# HM11.net
KiCad netlist of a schematic drawn in EAGLE
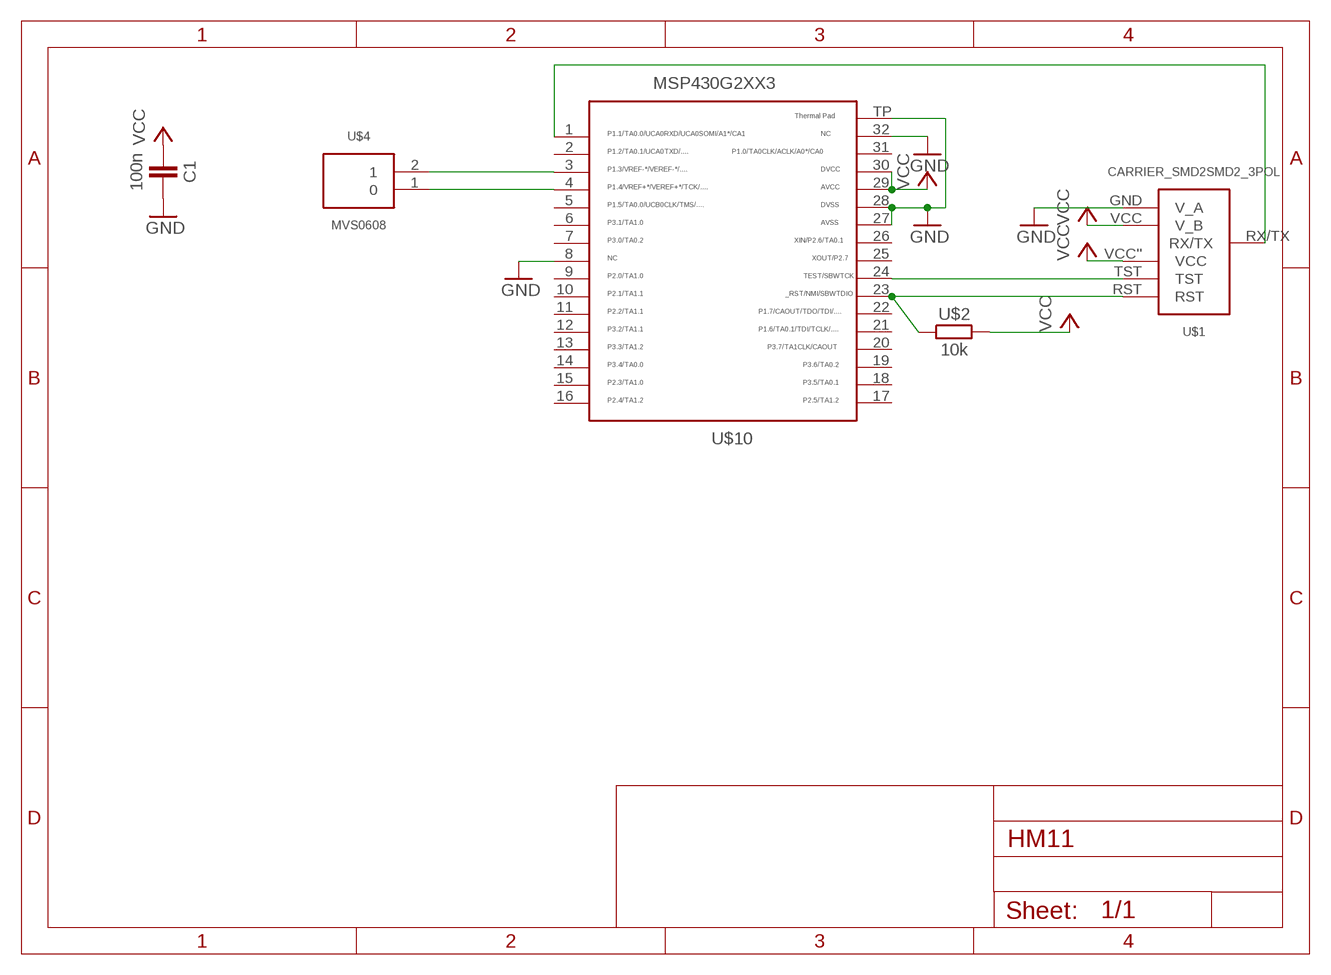
[diagram p0: schematic, sheet 1]

(export (version "E")
  (design (tool "Eeschema 10.0.6"))
  (components
    (comp (ref "C1")
      (value "100n")
      (footprint "eagle-import:603")
      (libsource (lib "eagle-import") (part "CAPACITOR"))
    )
    (comp (ref "U$1")
      (value "CARRIER_SMD2SMD2_3POL")
      (footprint "eagle-import:CARRIER_SMD2_3POL")
      (libsource (lib "eagle-import") (part "CARRIER_SMD2SMD2_3POL"))
    )
    (comp (ref "U$2")
      (value "10k")
      (footprint "eagle-import:603")
      (libsource (lib "eagle-import") (part "RESISTOR0603"))
    )
    (comp (ref "U$4")
      (value "MVS0608")
      (footprint "eagle-import:MVS06O8")
      (libsource (lib "eagle-import") (part "MVS0608"))
    )
    (comp (ref "U$10")
      (value "MSP430G2553")
      (footprint "eagle-import:QFN32")
      (libsource (lib "eagle-import") (part "MSP430G2553"))
    )
  )
  (nets
    (net (code "1") (name "GND") (class "Default")
      (node (ref "C1") (pin "2") (pinfunction "2_2") (pintype "passive"))
      (node (ref "U$1") (pin "GND") (pinfunction "V_A_GND") (pintype "bidirectional"))
      (node (ref "U$10") (pin "27") (pinfunction "27_27") (pintype "bidirectional"))
      (node (ref "U$10") (pin "28") (pinfunction "28_28") (pintype "bidirectional"))
      (node (ref "U$10") (pin "32") (pinfunction "32_32") (pintype "bidirectional"))
      (node (ref "U$10") (pin "8") (pinfunction "8_8") (pintype "bidirectional"))
      (node (ref "U$10") (pin "TP") (pinfunction "TP_TP") (pintype "bidirectional"))
    )
    (net (code "2") (name "Net-(U$1-PadRST)") (class "Default")
      (node (ref "U$1") (pin "RST") (pinfunction "RST_RST") (pintype "bidirectional"))
      (node (ref "U$10") (pin "23") (pinfunction "23_23") (pintype "bidirectional"))
      (node (ref "U$2") (pin "1") (pinfunction "1_1") (pintype "passive"))
    )
    (net (code "3") (name "Net-(U$1-PadRX{slash}TX)") (class "Default")
      (node (ref "U$1") (pin "RX/TX") (pinfunction "RX/TX_RX/TX") (pintype "bidirectional"))
      (node (ref "U$10") (pin "1") (pinfunction "1_1") (pintype "bidirectional"))
    )
    (net (code "4") (name "Net-(U$1-PadTST)") (class "Default")
      (node (ref "U$1") (pin "TST") (pinfunction "TST_TST") (pintype "bidirectional"))
      (node (ref "U$10") (pin "24") (pinfunction "24_24") (pintype "bidirectional"))
    )
    (net (code "5") (name "Net-(U$4-0)") (class "Default")
      (node (ref "U$10") (pin "4") (pinfunction "4_4") (pintype "bidirectional"))
      (node (ref "U$4") (pin "1") (pinfunction "0_1") (pintype "bidirectional"))
    )
    (net (code "6") (name "Net-(U$4-1)") (class "Default")
      (node (ref "U$10") (pin "3") (pinfunction "3_3") (pintype "bidirectional"))
      (node (ref "U$4") (pin "2") (pinfunction "1_2") (pintype "bidirectional"))
    )
    (net (code "7") (name "VCC") (class "Default")
      (node (ref "C1") (pin "1") (pinfunction "1_1") (pintype "passive"))
      (node (ref "U$1") (pin "VCC") (pinfunction "V_B_VCC") (pintype "bidirectional"))
      (node (ref "U$1") (pin "VCC''") (pinfunction "VCC_VCC''") (pintype "bidirectional"))
      (node (ref "U$10") (pin "29") (pinfunction "29_29") (pintype "bidirectional"))
      (node (ref "U$10") (pin "30") (pinfunction "30_30") (pintype "bidirectional"))
      (node (ref "U$2") (pin "2") (pinfunction "2_2") (pintype "passive"))
    )
    (net (code "8") (name "unconnected-(U$10-Pad2)") (class "Default")
      (node (ref "U$10") (pin "2") (pinfunction "2_2") (pintype "bidirectional"))
    )
    (net (code "9") (name "unconnected-(U$10-Pad5)") (class "Default")
      (node (ref "U$10") (pin "5") (pinfunction "5_5") (pintype "bidirectional"))
    )
    (net (code "10") (name "unconnected-(U$10-Pad6)") (class "Default")
      (node (ref "U$10") (pin "6") (pinfunction "6_6") (pintype "bidirectional"))
    )
    (net (code "11") (name "unconnected-(U$10-Pad7)") (class "Default")
      (node (ref "U$10") (pin "7") (pinfunction "7_7") (pintype "bidirectional"))
    )
    (net (code "12") (name "unconnected-(U$10-Pad9)") (class "Default")
      (node (ref "U$10") (pin "9") (pinfunction "9_9") (pintype "bidirectional"))
    )
    (net (code "13") (name "unconnected-(U$10-Pad10)") (class "Default")
      (node (ref "U$10") (pin "10") (pinfunction "10_10") (pintype "bidirectional"))
    )
    (net (code "14") (name "unconnected-(U$10-Pad11)") (class "Default")
      (node (ref "U$10") (pin "11") (pinfunction "11_11") (pintype "bidirectional"))
    )
    (net (code "15") (name "unconnected-(U$10-Pad12)") (class "Default")
      (node (ref "U$10") (pin "12") (pinfunction "12_12") (pintype "bidirectional"))
    )
    (net (code "16") (name "unconnected-(U$10-Pad13)") (class "Default")
      (node (ref "U$10") (pin "13") (pinfunction "13_13") (pintype "bidirectional"))
    )
    (net (code "17") (name "unconnected-(U$10-Pad14)") (class "Default")
      (node (ref "U$10") (pin "14") (pinfunction "14_14") (pintype "bidirectional"))
    )
    (net (code "18") (name "unconnected-(U$10-Pad15)") (class "Default")
      (node (ref "U$10") (pin "15") (pinfunction "15_15") (pintype "bidirectional"))
    )
    (net (code "19") (name "unconnected-(U$10-Pad16)") (class "Default")
      (node (ref "U$10") (pin "16") (pinfunction "16_16") (pintype "bidirectional"))
    )
    (net (code "20") (name "unconnected-(U$10-Pad17)") (class "Default")
      (node (ref "U$10") (pin "17") (pinfunction "17_17") (pintype "bidirectional"))
    )
    (net (code "21") (name "unconnected-(U$10-Pad18)") (class "Default")
      (node (ref "U$10") (pin "18") (pinfunction "18_18") (pintype "bidirectional"))
    )
    (net (code "22") (name "unconnected-(U$10-Pad19)") (class "Default")
      (node (ref "U$10") (pin "19") (pinfunction "19_19") (pintype "bidirectional"))
    )
    (net (code "23") (name "unconnected-(U$10-Pad20)") (class "Default")
      (node (ref "U$10") (pin "20") (pinfunction "20_20") (pintype "bidirectional"))
    )
    (net (code "24") (name "unconnected-(U$10-Pad21)") (class "Default")
      (node (ref "U$10") (pin "21") (pinfunction "21_21") (pintype "bidirectional"))
    )
    (net (code "25") (name "unconnected-(U$10-Pad22)") (class "Default")
      (node (ref "U$10") (pin "22") (pinfunction "22_22") (pintype "bidirectional"))
    )
    (net (code "26") (name "unconnected-(U$10-Pad25)") (class "Default")
      (node (ref "U$10") (pin "25") (pinfunction "25_25") (pintype "bidirectional"))
    )
    (net (code "27") (name "unconnected-(U$10-Pad26)") (class "Default")
      (node (ref "U$10") (pin "26") (pinfunction "26_26") (pintype "bidirectional"))
    )
    (net (code "28") (name "unconnected-(U$10-Pad31)") (class "Default")
      (node (ref "U$10") (pin "31") (pinfunction "31_31") (pintype "bidirectional"))
    )
  )
)
